# VoltageR.net
KiCad netlist of a schematic drawn in Altium Designer
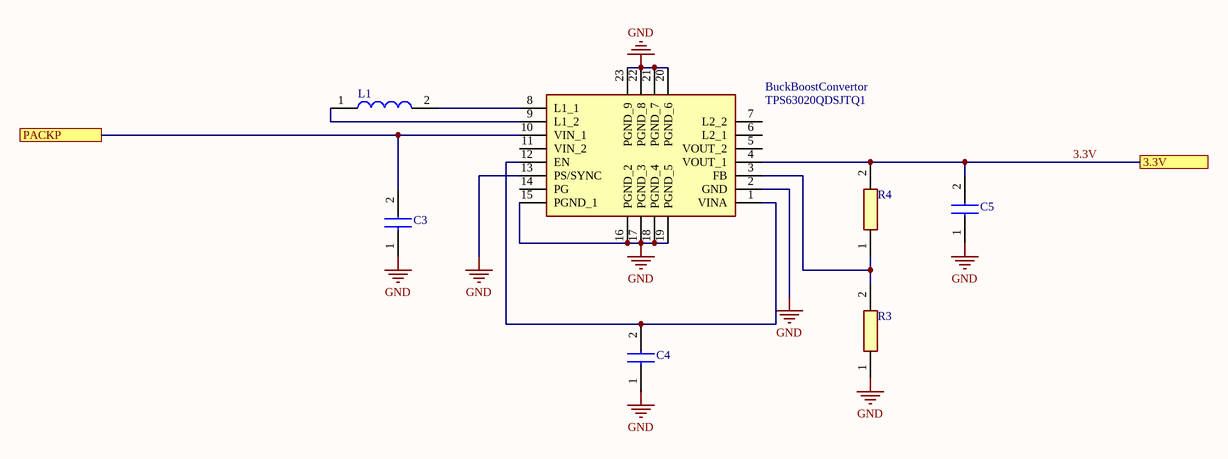
[diagram p0: VoltageR.SchDoc]

(export (version "E")
  (design (tool "Eeschema 10.0.6"))
  (components
    (comp (ref "BuckBoostConvertor")
      (value "TPS63020QDSJTQ1")
      (footprint "SamacSys:TPS63020QDSJTQ1")
      (description "Integrated Circuit")
      (fields (field (name "MOUSER PART NUMBER") "595-TPS63020QDSJTQ1"))
      (libsource (lib "*") (part "TPS63020QDSJTQ1"))
    )
    (comp (ref "C3")
      (value "C0603C150K5GAC")
      (footprint "SamacSys:CAPC1608X87N")
      (description "Capacitor")
      (fields (field (name "MOUSER PART NUMBER") "80-C0603C150K5GAC"))
      (libsource (lib "*") (part "C0603C150K5GAC"))
    )
    (comp (ref "C4")
      (value "C0603C150K5GAC")
      (footprint "SamacSys:CAPC1608X87N")
      (description "Capacitor")
      (fields (field (name "MOUSER PART NUMBER") "80-C0603C150K5GAC"))
      (libsource (lib "*") (part "C0603C150K5GAC"))
    )
    (comp (ref "C5")
      (value "C0603C150K5GAC")
      (footprint "SamacSys:CAPC1608X87N")
      (description "Capacitor")
      (fields (field (name "MOUSER PART NUMBER") "80-C0603C150K5GAC"))
      (libsource (lib "*") (part "C0603C150K5GAC"))
    )
    (comp (ref "L1")
      (value "0603CS-47NXGLU")
      (footprint "SamacSys:0603CS82NXGLW")
      (description "Inductor")
      (fields (field (name "MOUSER PART NUMBER") "994-0603CS-47NXGLU"))
      (libsource (lib "*") (part "0603CS-47NXGLU"))
    )
    (comp (ref "R3")
      (value "CRCW06034K70JNEA")
      (footprint "SamacSys:RESC1608X50N")
      (description "Resistor")
      (fields (field (name "MOUSER PART NUMBER") "71-CRCW0603J-4.7K-E3"))
      (libsource (lib "*") (part "CRCW06034K70JNEA"))
    )
    (comp (ref "R4")
      (value "CRCW06034K70JNEA")
      (footprint "SamacSys:RESC1608X50N")
      (description "Resistor")
      (fields (field (name "MOUSER PART NUMBER") "71-CRCW0603J-4.7K-E3"))
      (libsource (lib "*") (part "CRCW06034K70JNEA"))
    )
  )
  (nets
    (net (code "1") (name "/3.3V") (class "Default")
      (node (ref "BuckBoostConvertor") (pin "4") (pinfunction "VOUT_1_4") (pintype "passive"))
      (node (ref "C5") (pin "2") (pinfunction "2_2") (pintype "passive"))
      (node (ref "R4") (pin "2") (pinfunction "2_2") (pintype "passive"))
    )
    (net (code "2") (name "/PACKP") (class "Default")
      (node (ref "BuckBoostConvertor") (pin "10") (pinfunction "VIN_1_10") (pintype "passive"))
      (node (ref "C3") (pin "2") (pinfunction "2_2") (pintype "passive"))
    )
    (net (code "3") (name "GND") (class "Default")
      (node (ref "BuckBoostConvertor") (pin "13") (pinfunction "PS/SYNC_13") (pintype "passive"))
      (node (ref "BuckBoostConvertor") (pin "15") (pinfunction "PGND_1_15") (pintype "passive"))
      (node (ref "BuckBoostConvertor") (pin "16") (pinfunction "PGND_2_16") (pintype "passive"))
      (node (ref "BuckBoostConvertor") (pin "17") (pinfunction "PGND_3_17") (pintype "passive"))
      (node (ref "BuckBoostConvertor") (pin "18") (pinfunction "PGND_4_18") (pintype "passive"))
      (node (ref "BuckBoostConvertor") (pin "19") (pinfunction "PGND_5_19") (pintype "passive"))
      (node (ref "BuckBoostConvertor") (pin "2") (pinfunction "GND_2") (pintype "passive"))
      (node (ref "BuckBoostConvertor") (pin "20") (pinfunction "PGND_6_20") (pintype "passive"))
      (node (ref "BuckBoostConvertor") (pin "21") (pinfunction "PGND_7_21") (pintype "passive"))
      (node (ref "BuckBoostConvertor") (pin "22") (pinfunction "PGND_8_22") (pintype "passive"))
      (node (ref "BuckBoostConvertor") (pin "23") (pinfunction "PGND_9_23") (pintype "passive"))
      (node (ref "C3") (pin "1") (pinfunction "1_1") (pintype "passive"))
      (node (ref "C4") (pin "1") (pinfunction "1_1") (pintype "passive"))
      (node (ref "C5") (pin "1") (pinfunction "1_1") (pintype "passive"))
      (node (ref "R3") (pin "1") (pinfunction "1_1") (pintype "passive"))
    )
    (net (code "4") (name "Net-(BuckBoostConvertor-EN)") (class "Default")
      (node (ref "BuckBoostConvertor") (pin "1") (pinfunction "VINA_1") (pintype "passive"))
      (node (ref "BuckBoostConvertor") (pin "12") (pinfunction "EN_12") (pintype "passive"))
      (node (ref "C4") (pin "2") (pinfunction "2_2") (pintype "passive"))
    )
    (net (code "5") (name "Net-(BuckBoostConvertor-FB)") (class "Default")
      (node (ref "BuckBoostConvertor") (pin "3") (pinfunction "FB_3") (pintype "passive"))
      (node (ref "R3") (pin "2") (pinfunction "2_2") (pintype "passive"))
      (node (ref "R4") (pin "1") (pinfunction "1_1") (pintype "passive"))
    )
    (net (code "6") (name "Net-(BuckBoostConvertor-L1_1)") (class "Default")
      (node (ref "BuckBoostConvertor") (pin "8") (pinfunction "L1_1_8") (pintype "passive"))
      (node (ref "L1") (pin "2") (pinfunction "2_2") (pintype "passive"))
    )
    (net (code "7") (name "Net-(BuckBoostConvertor-L1_2)") (class "Default")
      (node (ref "BuckBoostConvertor") (pin "9") (pinfunction "L1_2_9") (pintype "passive"))
      (node (ref "L1") (pin "1") (pinfunction "1_1") (pintype "passive"))
    )
    (net (code "8") (name "unconnected-(BuckBoostConvertor-L2_1-Pad6)") (class "Default")
      (node (ref "BuckBoostConvertor") (pin "6") (pinfunction "L2_1_6") (pintype "passive"))
    )
    (net (code "9") (name "unconnected-(BuckBoostConvertor-L2_2-Pad7)") (class "Default")
      (node (ref "BuckBoostConvertor") (pin "7") (pinfunction "L2_2_7") (pintype "passive"))
    )
    (net (code "10") (name "unconnected-(BuckBoostConvertor-PG-Pad14)") (class "Default")
      (node (ref "BuckBoostConvertor") (pin "14") (pinfunction "PG_14") (pintype "passive"))
    )
    (net (code "11") (name "unconnected-(BuckBoostConvertor-VIN_2-Pad11)") (class "Default")
      (node (ref "BuckBoostConvertor") (pin "11") (pinfunction "VIN_2_11") (pintype "passive"))
    )
    (net (code "12") (name "unconnected-(BuckBoostConvertor-VOUT_2-Pad5)") (class "Default")
      (node (ref "BuckBoostConvertor") (pin "5") (pinfunction "VOUT_2_5") (pintype "passive"))
    )
  )
)
